# untitled.net
KiCad netlist of a schematic drawn in EAGLE
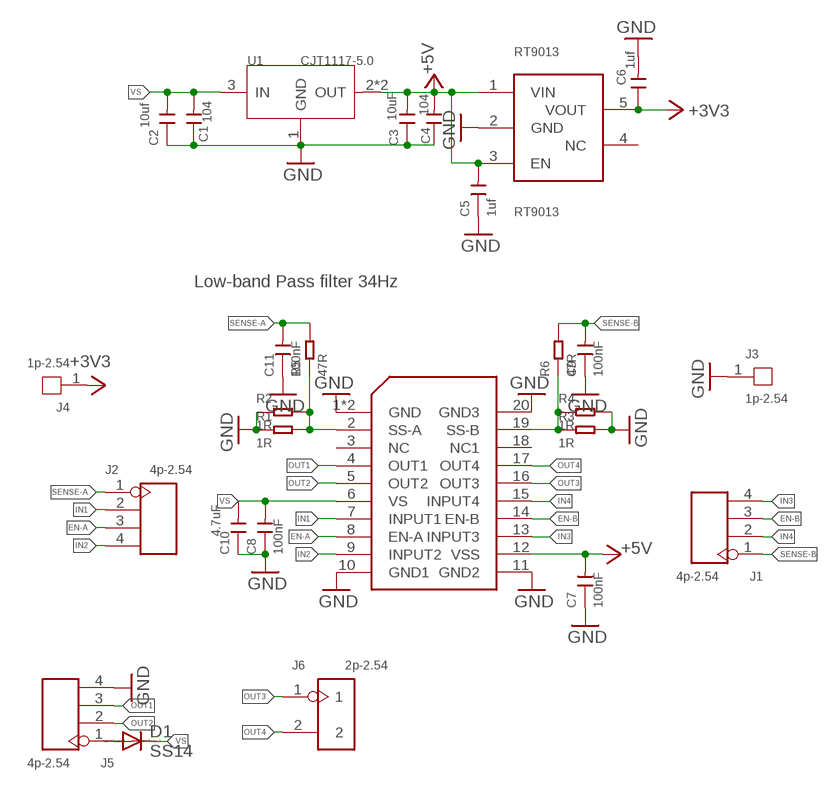
[diagram p0: schematic, sheet 1]

(export (version "E")
  (design (tool "Eeschema 10.0.6"))
  (components
    (comp (ref "C1")
      (value "104")
      (footprint "eagle-import:C0402")
      (fields (field (name "MPN") "GRM1555C1H150JA01D"))
      (libsource (lib "eagle-import") (part "CAP-(0402)"))
    )
    (comp (ref "C2")
      (value "10uf")
      (footprint "eagle-import:C0402")
      (fields (field (name "MPN") "GRM1555C1H150JA01D"))
      (libsource (lib "eagle-import") (part "CAP-(0402)"))
    )
    (comp (ref "C3")
      (value "10uF")
      (footprint "eagle-import:C0402")
      (fields (field (name "MPN") "GRM1555C1H150JA01D"))
      (libsource (lib "eagle-import") (part "CAP-(0402)"))
    )
    (comp (ref "C4")
      (value "104")
      (footprint "eagle-import:C0402")
      (fields (field (name "MPN") "GRM1555C1H150JA01D"))
      (libsource (lib "eagle-import") (part "CAP-(0402)"))
    )
    (comp (ref "C5")
      (value "1uf")
      (footprint "eagle-import:C0402")
      (fields (field (name "MPN") "GRM1555C1H150JA01D"))
      (libsource (lib "eagle-import") (part "CAP-(0402)"))
    )
    (comp (ref "C6")
      (value "1uf")
      (footprint "eagle-import:C0402")
      (fields (field (name "MPN") "GRM1555C1H150JA01D"))
      (libsource (lib "eagle-import") (part "CAP-(0402)"))
    )
    (comp (ref "C7")
      (value "100nF")
      (footprint "eagle-import:C0402")
      (fields (field (name "MPN") "GRM1555C1H150JA01D"))
      (libsource (lib "eagle-import") (part "CAP-(0402)"))
    )
    (comp (ref "C8")
      (value "100nF")
      (footprint "eagle-import:C0402")
      (fields (field (name "MPN") "GRM1555C1H150JA01D"))
      (libsource (lib "eagle-import") (part "CAP-(0402)"))
    )
    (comp (ref "C9")
      (value "100nF")
      (footprint "eagle-import:C0402")
      (fields (field (name "MPN") "GRM1555C1H150JA01D"))
      (libsource (lib "eagle-import") (part "CAP-(0402)"))
    )
    (comp (ref "C10")
      (value "4.7uF")
      (footprint "eagle-import:C0402")
      (fields (field (name "MPN") "GRM1555C1H150JA01D"))
      (libsource (lib "eagle-import") (part "CAP-(0402)"))
    )
    (comp (ref "C11")
      (value "100nF")
      (footprint "eagle-import:C0402")
      (fields (field (name "MPN") "GRM1555C1H150JA01D"))
      (libsource (lib "eagle-import") (part "CAP-(0402)"))
    )
    (comp (ref "D1")
      (value "SS14")
      (footprint "eagle-import:SMA")
      (libsource (lib "eagle-import") (part "SS14"))
    )
    (comp (ref "J1")
      (value "4p-2.54")
      (footprint "eagle-import:H4-2.54")
      (fields (field (name "MPN") "F185-1104A1BSYA1"))
      (libsource (lib "eagle-import") (part "DIP-BLACK-FEMALE-HEADER-VERT(4P-2.54)"))
    )
    (comp (ref "J2")
      (value "4p-2.54")
      (footprint "eagle-import:H4-2.54")
      (fields (field (name "MPN") "F185-1104A1BSYA1"))
      (libsource (lib "eagle-import") (part "DIP-BLACK-FEMALE-HEADER-VERT(4P-2.54)"))
    )
    (comp (ref "J3")
      (value "1p-2.54")
      (footprint "eagle-import:1P-65_35MIL")
      (fields (field (name "MPN") "RF130-1013BBS0741"))
      (libsource (lib "eagle-import") (part "DIP-BLACK-ROUND-FEMALE-HEADER-VERT(1P-2.54)"))
    )
    (comp (ref "J4")
      (value "1p-2.54")
      (footprint "eagle-import:1P-65_35MIL")
      (fields (field (name "MPN") "RF130-1013BBS0741"))
      (libsource (lib "eagle-import") (part "DIP-BLACK-ROUND-FEMALE-HEADER-VERT(1P-2.54)"))
    )
    (comp (ref "J5")
      (value "4p-2.54")
      (footprint "eagle-import:H4-2.54")
      (fields (field (name "MPN") "F185-1104A1BSYA1"))
      (libsource (lib "eagle-import") (part "DIP-BLACK-FEMALE-HEADER-VERT(4P-2.54)"))
    )
    (comp (ref "J6")
      (value "2p-2.54")
      (footprint "eagle-import:H2-2.54")
      (fields (field (name "MPN") "RF130-1023ABS0741"))
      (libsource (lib "eagle-import") (part "DIP-BLACK-ROUND-FEMALE-HEADER-VERT(2P-2.54)"))
    )
    (comp (ref "P-1")
      (value "L298P")
      (footprint "eagle-import:POWERSO-20")
      (libsource (lib "eagle-import") (part "L298P"))
    )
    (comp (ref "R1")
      (value "1R")
      (footprint "eagle-import:R0402")
      (fields (field (name "MPN") "RC0402JR-070RL"))
      (libsource (lib "eagle-import") (part "RES-(0402)"))
    )
    (comp (ref "R2")
      (value "1R")
      (footprint "eagle-import:R0402")
      (fields (field (name "MPN") "RC0402JR-070RL"))
      (libsource (lib "eagle-import") (part "RES-(0402)"))
    )
    (comp (ref "R3")
      (value "1R")
      (footprint "eagle-import:R0402")
      (fields (field (name "MPN") "RC0402JR-070RL"))
      (libsource (lib "eagle-import") (part "RES-(0402)"))
    )
    (comp (ref "R4")
      (value "1R")
      (footprint "eagle-import:R0402")
      (fields (field (name "MPN") "RC0402JR-070RL"))
      (libsource (lib "eagle-import") (part "RES-(0402)"))
    )
    (comp (ref "R5")
      (value "47R")
      (footprint "eagle-import:R0402")
      (fields (field (name "MPN") "RC0402JR-070RL"))
      (libsource (lib "eagle-import") (part "RES-(0402)"))
    )
    (comp (ref "R6")
      (value "47R")
      (footprint "eagle-import:R0402")
      (fields (field (name "MPN") "RC0402JR-070RL"))
      (libsource (lib "eagle-import") (part "RES-(0402)"))
    )
    (comp (ref "RT9013")
      (value "RT9013")
      (footprint "eagle-import:SOT23-5")
      (libsource (lib "eagle-import") (part "RT9013"))
    )
    (comp (ref "U1")
      (value "CJT1117-5.0")
      (footprint "eagle-import:SOT-223")
      (fields (field (name "MPN") "CJT1117-3.3"))
      (libsource (lib "eagle-import") (part "PMIC-CJT1117-3.3(SOT223)"))
    )
  )
  (nets
    (net (code "1") (name "+3V3") (class "Default")
      (node (ref "C6") (pin "1") (pinfunction "1_1") (pintype "passive"))
      (node (ref "J4") (pin "1") (pinfunction "1_1") (pintype "bidirectional"))
      (node (ref "RT9013") (pin "5") (pinfunction "VOUT_5") (pintype "bidirectional"))
    )
    (net (code "2") (name "+5V") (class "Default")
      (node (ref "C3") (pin "2") (pinfunction "2_2") (pintype "passive"))
      (node (ref "C4") (pin "2") (pinfunction "2_2") (pintype "passive"))
      (node (ref "C5") (pin "2") (pinfunction "2_2") (pintype "passive"))
      (node (ref "C7") (pin "2") (pinfunction "2_2") (pintype "passive"))
      (node (ref "P-1") (pin "12") (pinfunction "VSS_12") (pintype "bidirectional"))
      (node (ref "RT9013") (pin "1") (pinfunction "VIN_1") (pintype "bidirectional"))
      (node (ref "RT9013") (pin "3") (pinfunction "EN_3") (pintype "bidirectional"))
      (node (ref "U1") (pin "2") (pinfunction "OUT_2") (pintype "bidirectional"))
      (node (ref "U1") (pin "TER") (pinfunction "OUT_TER") (pintype "bidirectional"))
    )
    (net (code "3") (name "EN-A") (class "Default")
      (node (ref "J2") (pin "3") (pinfunction "P$3_3") (pintype "bidirectional"))
      (node (ref "P-1") (pin "8") (pinfunction "EN-A_8") (pintype "bidirectional"))
    )
    (net (code "4") (name "EN-B") (class "Default")
      (node (ref "J1") (pin "3") (pinfunction "P$3_3") (pintype "bidirectional"))
      (node (ref "P-1") (pin "14") (pinfunction "EN-B_14") (pintype "bidirectional"))
    )
    (net (code "5") (name "GND") (class "Default")
      (node (ref "C1") (pin "1") (pinfunction "1_1") (pintype "passive"))
      (node (ref "C10") (pin "1") (pinfunction "1_1") (pintype "passive"))
      (node (ref "C11") (pin "1") (pinfunction "1_1") (pintype "passive"))
      (node (ref "C2") (pin "1") (pinfunction "1_1") (pintype "passive"))
      (node (ref "C3") (pin "1") (pinfunction "1_1") (pintype "passive"))
      (node (ref "C4") (pin "1") (pinfunction "1_1") (pintype "passive"))
      (node (ref "C5") (pin "1") (pinfunction "1_1") (pintype "passive"))
      (node (ref "C6") (pin "2") (pinfunction "2_2") (pintype "passive"))
      (node (ref "C7") (pin "1") (pinfunction "1_1") (pintype "passive"))
      (node (ref "C8") (pin "1") (pinfunction "1_1") (pintype "passive"))
      (node (ref "C9") (pin "1") (pinfunction "1_1") (pintype "passive"))
      (node (ref "J3") (pin "1") (pinfunction "1_1") (pintype "bidirectional"))
      (node (ref "J5") (pin "4") (pinfunction "P$4_4") (pintype "bidirectional"))
      (node (ref "P-1") (pin "1") (pinfunction "GND_1") (pintype "bidirectional"))
      (node (ref "P-1") (pin "10") (pinfunction "GND1_10") (pintype "bidirectional"))
      (node (ref "P-1") (pin "11") (pinfunction "GND2_11") (pintype "bidirectional"))
      (node (ref "P-1") (pin "20") (pinfunction "GND3_20") (pintype "bidirectional"))
      (node (ref "P-1") (pin "GND") (pinfunction "GND_GND") (pintype "bidirectional"))
      (node (ref "R1") (pin "1") (pinfunction "1_1") (pintype "passive"))
      (node (ref "R2") (pin "1") (pinfunction "1_1") (pintype "passive"))
      (node (ref "R3") (pin "2") (pinfunction "2_2") (pintype "passive"))
      (node (ref "R4") (pin "2") (pinfunction "2_2") (pintype "passive"))
      (node (ref "RT9013") (pin "2") (pinfunction "GND_2") (pintype "bidirectional"))
      (node (ref "U1") (pin "1") (pinfunction "GND_1") (pintype "bidirectional"))
    )
    (net (code "6") (name "IN1") (class "Default")
      (node (ref "J2") (pin "2") (pinfunction "P$2_2") (pintype "bidirectional"))
      (node (ref "P-1") (pin "7") (pinfunction "INPUT1_7") (pintype "bidirectional"))
    )
    (net (code "7") (name "IN2") (class "Default")
      (node (ref "J2") (pin "4") (pinfunction "P$4_4") (pintype "bidirectional"))
      (node (ref "P-1") (pin "9") (pinfunction "INPUT2_9") (pintype "bidirectional"))
    )
    (net (code "8") (name "IN3") (class "Default")
      (node (ref "J1") (pin "4") (pinfunction "P$4_4") (pintype "bidirectional"))
      (node (ref "P-1") (pin "13") (pinfunction "INPUT3_13") (pintype "bidirectional"))
    )
    (net (code "9") (name "IN4") (class "Default")
      (node (ref "J1") (pin "2") (pinfunction "P$2_2") (pintype "bidirectional"))
      (node (ref "P-1") (pin "15") (pinfunction "INPUT4_15") (pintype "bidirectional"))
    )
    (net (code "10") (name "Net-(J5-P$1)") (class "Default")
      (node (ref "D1") (pin "A") (pinfunction "A_A") (pintype "passive"))
      (node (ref "J5") (pin "1") (pinfunction "P$1_1") (pintype "bidirectional"))
    )
    (net (code "11") (name "Net-(P-1-SS-A)") (class "Default")
      (node (ref "P-1") (pin "2") (pinfunction "SS-A_2") (pintype "bidirectional"))
      (node (ref "R1") (pin "2") (pinfunction "2_2") (pintype "passive"))
      (node (ref "R2") (pin "2") (pinfunction "2_2") (pintype "passive"))
      (node (ref "R5") (pin "1") (pinfunction "1_1") (pintype "passive"))
    )
    (net (code "12") (name "Net-(P-1-SS-B)") (class "Default")
      (node (ref "P-1") (pin "19") (pinfunction "SS-B_19") (pintype "bidirectional"))
      (node (ref "R3") (pin "1") (pinfunction "1_1") (pintype "passive"))
      (node (ref "R4") (pin "1") (pinfunction "1_1") (pintype "passive"))
      (node (ref "R6") (pin "1") (pinfunction "1_1") (pintype "passive"))
    )
    (net (code "13") (name "OUT1") (class "Default")
      (node (ref "J5") (pin "3") (pinfunction "P$3_3") (pintype "bidirectional"))
      (node (ref "P-1") (pin "4") (pinfunction "OUT1_4") (pintype "bidirectional"))
    )
    (net (code "14") (name "OUT2") (class "Default")
      (node (ref "J5") (pin "2") (pinfunction "P$2_2") (pintype "bidirectional"))
      (node (ref "P-1") (pin "5") (pinfunction "OUT2_5") (pintype "bidirectional"))
    )
    (net (code "15") (name "OUT3") (class "Default")
      (node (ref "J6") (pin "1") (pinfunction "1_1") (pintype "bidirectional"))
      (node (ref "P-1") (pin "16") (pinfunction "OUT3_16") (pintype "bidirectional"))
    )
    (net (code "16") (name "OUT4") (class "Default")
      (node (ref "J6") (pin "2") (pinfunction "2_2") (pintype "bidirectional"))
      (node (ref "P-1") (pin "17") (pinfunction "OUT4_17") (pintype "bidirectional"))
    )
    (net (code "17") (name "SENSE-A") (class "Default")
      (node (ref "C11") (pin "2") (pinfunction "2_2") (pintype "passive"))
      (node (ref "J2") (pin "1") (pinfunction "P$1_1") (pintype "bidirectional"))
      (node (ref "R5") (pin "2") (pinfunction "2_2") (pintype "passive"))
    )
    (net (code "18") (name "SENSE-B") (class "Default")
      (node (ref "C9") (pin "2") (pinfunction "2_2") (pintype "passive"))
      (node (ref "J1") (pin "1") (pinfunction "P$1_1") (pintype "bidirectional"))
      (node (ref "R6") (pin "2") (pinfunction "2_2") (pintype "passive"))
    )
    (net (code "19") (name "VS") (class "Default")
      (node (ref "C1") (pin "2") (pinfunction "2_2") (pintype "passive"))
      (node (ref "C10") (pin "2") (pinfunction "2_2") (pintype "passive"))
      (node (ref "C2") (pin "2") (pinfunction "2_2") (pintype "passive"))
      (node (ref "C8") (pin "2") (pinfunction "2_2") (pintype "passive"))
      (node (ref "D1") (pin "C") (pinfunction "C_C") (pintype "passive"))
      (node (ref "P-1") (pin "6") (pinfunction "VS_6") (pintype "bidirectional"))
      (node (ref "U1") (pin "3") (pinfunction "IN_3") (pintype "bidirectional"))
    )
    (net (code "20") (name "unconnected-(P-1-NC-Pad3)") (class "Default")
      (node (ref "P-1") (pin "3") (pinfunction "NC_3") (pintype "bidirectional"))
    )
    (net (code "21") (name "unconnected-(P-1-NC1-Pad18)") (class "Default")
      (node (ref "P-1") (pin "18") (pinfunction "NC1_18") (pintype "bidirectional"))
    )
    (net (code "22") (name "unconnected-(RT9013-NC-Pad4)") (class "Default")
      (node (ref "RT9013") (pin "4") (pinfunction "NC_4") (pintype "bidirectional"))
    )
  )
)
